# Battery.net
KiCad netlist of a schematic drawn in Altium Designer
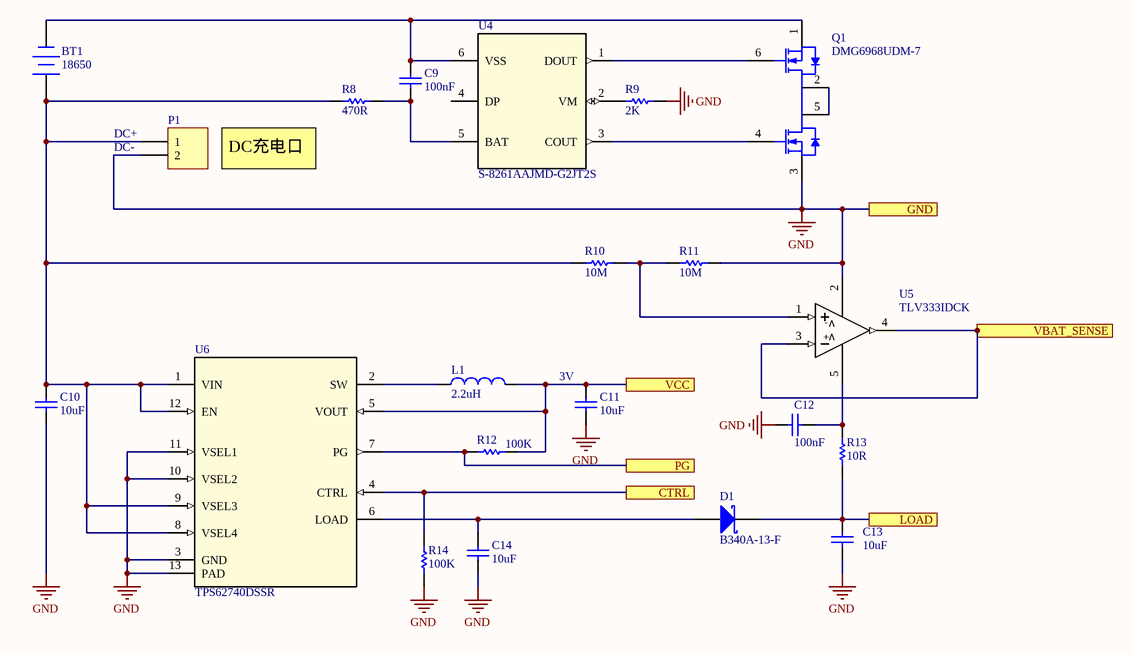
[diagram p0: Battery.SchDoc]

(export (version "E")
  (design (tool "Eeschema 10.0.6"))
  (components
    (comp (ref "BT1")
      (value "18650")
      (footprint "CP1X2")
      (description "18650单节直插电池仓")
      (libsource (lib "00Lib") (part "Battery_18650_DIP"))
    )
    (comp (ref "C9")
      (value "100nF")
      (footprint "R0603_C")
      (description "精度 ±10% \r\n容值 100nF \r\n额定电压 50V \r\n温漂系数（介质材料) X7R")
      (libsource (lib "00Lib") (part "100nF/0603/50V"))
    )
    (comp (ref "C10")
      (value "10uF")
      (footprint "R0805_C")
      (description "精度 ±10% \r\n容值 10uF \r\n额定电压 16V \r\n温漂系数（介质材料) X7R")
      (libsource (lib "00Lib") (part "10uF/0805/16V"))
    )
    (comp (ref "C11")
      (value "10uF")
      (footprint "R0805_C")
      (description "精度 ±10% \r\n容值 10uF \r\n额定电压 16V \r\n温漂系数（介质材料) X7R")
      (libsource (lib "00Lib") (part "10uF/0805/16V"))
    )
    (comp (ref "C12")
      (value "100nF")
      (footprint "R0603_C")
      (description "精度 ±10% \r\n容值 100nF \r\n额定电压 50V \r\n温漂系数（介质材料) X7R")
      (libsource (lib "00Lib") (part "100nF/0603/50V"))
    )
    (comp (ref "C13")
      (value "10uF")
      (footprint "R0805_C")
      (description "精度 ±10% \r\n容值 10uF \r\n额定电压 16V \r\n温漂系数（介质材料) X7R")
      (libsource (lib "00Lib") (part "10uF/0805/16V"))
    )
    (comp (ref "C14")
      (value "10uF")
      (footprint "R0805_C")
      (description "精度 ±10% \r\n容值 10uF \r\n额定电压 16V \r\n温漂系数（介质材料) X7R")
      (libsource (lib "00Lib") (part "10uF/0805/16V"))
    )
    (comp (ref "D1")
      (value "B340A-13-F")
      (footprint "SMA(DO-214AC)_S2")
      (description "直流反向耐压（Vr） 40V \r\n平均整流电流（Io） 3A \r\n正向压降（Vf） 550mV @ 3A")
      (libsource (lib "00Lib") (part "B340A-13-F"))
    )
    (comp (ref "L1")
      (value "2.2uH")
      (footprint "NR2016")
      (description "精度 ±20% \r\n饱和电流 1.3A \r\n温升电流1.15A\r\n直流电阻（内阻） 175mΩ \r\n电感值 2.2uH")
      (libsource (lib "00Lib") (part "2.2uH/NR2016"))
    )
    (comp (ref "P1")
      (value "Header 2")
      (footprint "CP1X2")
      (description "Header, 2-Pin")
      (libsource (lib "00Lib") (part "Header 2"))
    )
    (comp (ref "Q1")
      (value "DMG6968UDM-7")
      (footprint "DBV0006A_N")
      (libsource (lib "00Lib") (part "DMG6968UDM-7"))
    )
    (comp (ref "R8")
      (value "470R")
      (footprint "R0603_R")
      (description "精度 ±1% \r\n温度系数 ±100ppm/℃ \r\n功率 0.1W")
      (libsource (lib "00Lib") (part "470R/0603"))
    )
    (comp (ref "R9")
      (value "2K")
      (footprint "R0603_R")
      (description "精度 ±1% \r\n阻值 2kΩ \r\n温度系数 ±100ppm/℃ \r\n功率 0.1W")
      (libsource (lib "00Lib") (part "2K/0603"))
    )
    (comp (ref "R10")
      (value "10M")
      (footprint "R0603_R")
      (description "温度系数 ±250ppm/℃ \r\n精度 ±1% \r\n阻值 10MΩ \r\n功率 0.1W")
      (libsource (lib "00Lib") (part "10M/0603"))
    )
    (comp (ref "R11")
      (value "10M")
      (footprint "R0603_R")
      (description "温度系数 ±250ppm/℃ \r\n精度 ±1% \r\n阻值 10MΩ \r\n功率 0.1W")
      (libsource (lib "00Lib") (part "10M/0603"))
    )
    (comp (ref "R12")
      (value "100K")
      (footprint "R0603_R")
      (description "精度 ±1% \r\n阻值 100kΩ \r\n温度系数 ±100ppm/℃ \r\n功率 0.1W")
      (libsource (lib "00Lib") (part "100K/0603"))
    )
    (comp (ref "R13")
      (value "10R")
      (footprint "R0603_R")
      (description "精度 ±1% \r\n阻值 10Ω \r\n温度系数 ±100ppm/℃ \r\n功率 0.1W")
      (libsource (lib "00Lib") (part "10R/0603"))
    )
    (comp (ref "R14")
      (value "100K")
      (footprint "R0603_R")
      (description "精度 ±1% \r\n阻值 100kΩ \r\n温度系数 ±100ppm/℃ \r\n功率 0.1W")
      (libsource (lib "00Lib") (part "100K/0603"))
    )
    (comp (ref "U4")
      (value "S-8261AAJMD-G2JT2S")
      (footprint "DBV0006A_N")
      (description "单节电池保护芯片\r\n过充4.325V\r\n过放2.5V\r\n过流150mV")
      (libsource (lib "00Lib") (part "S-8261AAJMD-G2JT2S"))
    )
    (comp (ref "U5")
      (value "TLV333IDCK")
      (footprint "DCK0005A_N")
      (description "电源电压 1.8V ~ 5.5V, ±0.9V ~ 2.75V\r\n增益带宽积（GBP） 350kHz \r\n压摆率（SR） 0.16 V/us \r\n工作温度 -40°C ~ 125°C")
      (libsource (lib "00Lib") (part "TLV333IDCK"))
    )
    (comp (ref "U6")
      (value "TPS62740DSSR")
      (footprint "DSS0012A")
      (description "DCDC")
      (libsource (lib "00Lib") (part "TPS62740DSSR"))
    )
  )
  (nets
    (net (code "1") (name "/CTRL") (class "Default")
      (node (ref "R14") (pin "2") (pinfunction "2_2") (pintype "passive"))
      (node (ref "U6") (pin "4") (pinfunction "CTRL_4") (pintype "input"))
    )
    (net (code "2") (name "/LOAD") (class "Default")
      (node (ref "C13") (pin "2") (pinfunction "2_2") (pintype "passive"))
      (node (ref "D1") (pin "2") (pinfunction "K_2") (pintype "passive"))
      (node (ref "R13") (pin "2") (pinfunction "2_2") (pintype "passive"))
    )
    (net (code "3") (name "/PG") (class "Default")
      (node (ref "R12") (pin "1") (pinfunction "1_1") (pintype "passive"))
      (node (ref "U6") (pin "7") (pinfunction "PG_7") (pintype "output"))
    )
    (net (code "4") (name "/VBAT_SENSE") (class "Default")
      (node (ref "U5") (pin "3") (pinfunction "IN-_3") (pintype "input"))
      (node (ref "U5") (pin "4") (pinfunction "OUT_4") (pintype "output"))
    )
    (net (code "5") (name "/VCC") (class "Default")
      (node (ref "C11") (pin "2") (pinfunction "2_2") (pintype "passive"))
      (node (ref "L1") (pin "2") (pinfunction "2_2") (pintype "passive"))
      (node (ref "R12") (pin "2") (pinfunction "2_2") (pintype "passive"))
      (node (ref "U6") (pin "5") (pinfunction "VOUT_5") (pintype "input"))
    )
    (net (code "6") (name "GND") (class "Default")
      (node (ref "C10") (pin "1") (pinfunction "1_1") (pintype "passive"))
      (node (ref "C11") (pin "1") (pinfunction "1_1") (pintype "passive"))
      (node (ref "C12") (pin "1") (pinfunction "1_1") (pintype "passive"))
      (node (ref "C13") (pin "1") (pinfunction "1_1") (pintype "passive"))
      (node (ref "C14") (pin "1") (pinfunction "1_1") (pintype "passive"))
      (node (ref "P1") (pin "2") (pinfunction "2_2") (pintype "passive"))
      (node (ref "Q1") (pin "3") (pinfunction "S2_3") (pintype "passive"))
      (node (ref "R11") (pin "1") (pinfunction "1_1") (pintype "passive"))
      (node (ref "R14") (pin "1") (pinfunction "1_1") (pintype "passive"))
      (node (ref "R9") (pin "2") (pinfunction "2_2") (pintype "passive"))
      (node (ref "U5") (pin "2") (pinfunction "V-_2") (pintype "power_in"))
      (node (ref "U6") (pin "10") (pinfunction "VSEL2_10") (pintype "input"))
      (node (ref "U6") (pin "11") (pinfunction "VSEL1_11") (pintype "input"))
      (node (ref "U6") (pin "13") (pinfunction "PAD_13") (pintype "power_in"))
      (node (ref "U6") (pin "3") (pinfunction "GND_3") (pintype "power_in"))
    )
    (net (code "7") (name "Net-(BT1-+)") (class "Default")
      (node (ref "BT1") (pin "1") (pinfunction "+_1") (pintype "passive"))
      (node (ref "C10") (pin "2") (pinfunction "2_2") (pintype "passive"))
      (node (ref "P1") (pin "1") (pinfunction "1_1") (pintype "passive"))
      (node (ref "R10") (pin "2") (pinfunction "2_2") (pintype "passive"))
      (node (ref "R8") (pin "1") (pinfunction "1_1") (pintype "passive"))
      (node (ref "U6") (pin "1") (pinfunction "VIN_1") (pintype "power_in"))
      (node (ref "U6") (pin "12") (pinfunction "EN_12") (pintype "input"))
      (node (ref "U6") (pin "8") (pinfunction "VSEL4_8") (pintype "input"))
      (node (ref "U6") (pin "9") (pinfunction "VSEL3_9") (pintype "input"))
    )
    (net (code "8") (name "Net-(BT1--)") (class "Default")
      (node (ref "BT1") (pin "2") (pinfunction "-_2") (pintype "passive"))
      (node (ref "C9") (pin "1") (pinfunction "1_1") (pintype "passive"))
      (node (ref "Q1") (pin "1") (pinfunction "S1_1") (pintype "passive"))
      (node (ref "U4") (pin "6") (pinfunction "VSS_6") (pintype "passive"))
    )
    (net (code "9") (name "Net-(D1-A)") (class "Default")
      (node (ref "C14") (pin "2") (pinfunction "2_2") (pintype "passive"))
      (node (ref "D1") (pin "1") (pinfunction "A_1") (pintype "passive"))
      (node (ref "U6") (pin "6") (pinfunction "LOAD_6") (pintype "power_in"))
    )
    (net (code "10") (name "Net-(Q1-D1{slash}D2-Pad2)") (class "Default")
      (node (ref "Q1") (pin "2") (pinfunction "D1/D2_2") (pintype "passive"))
      (node (ref "Q1") (pin "5") (pinfunction "D1/D2_5") (pintype "passive"))
    )
    (net (code "11") (name "Net-(Q1-G1)") (class "Default")
      (node (ref "Q1") (pin "6") (pinfunction "G1_6") (pintype "passive"))
      (node (ref "U4") (pin "1") (pinfunction "DOUT_1") (pintype "output"))
    )
    (net (code "12") (name "Net-(Q1-G2)") (class "Default")
      (node (ref "Q1") (pin "4") (pinfunction "G2_4") (pintype "passive"))
      (node (ref "U4") (pin "3") (pinfunction "COUT_3") (pintype "output"))
    )
    (net (code "13") (name "Net-(U4-BAT)") (class "Default")
      (node (ref "C9") (pin "2") (pinfunction "2_2") (pintype "passive"))
      (node (ref "R8") (pin "2") (pinfunction "2_2") (pintype "passive"))
      (node (ref "U4") (pin "5") (pinfunction "BAT_5") (pintype "power_in"))
    )
    (net (code "14") (name "Net-(U4-VM)") (class "Default")
      (node (ref "R9") (pin "1") (pinfunction "1_1") (pintype "passive"))
      (node (ref "U4") (pin "2") (pinfunction "VM_2") (pintype "bidirectional"))
    )
    (net (code "15") (name "Net-(U5-IN+)") (class "Default")
      (node (ref "R10") (pin "1") (pinfunction "1_1") (pintype "passive"))
      (node (ref "R11") (pin "2") (pinfunction "2_2") (pintype "passive"))
      (node (ref "U5") (pin "1") (pinfunction "IN+_1") (pintype "input"))
    )
    (net (code "16") (name "Net-(U5-V+)") (class "Default")
      (node (ref "C12") (pin "2") (pinfunction "2_2") (pintype "passive"))
      (node (ref "R13") (pin "1") (pinfunction "1_1") (pintype "passive"))
      (node (ref "U5") (pin "5") (pinfunction "V+_5") (pintype "power_in"))
    )
    (net (code "17") (name "Net-(U6-SW)") (class "Default")
      (node (ref "L1") (pin "1") (pinfunction "1_1") (pintype "passive"))
      (node (ref "U6") (pin "2") (pinfunction "SW_2") (pintype "power_in"))
    )
    (net (code "18") (name "unconnected-(U4-DP-Pad4)") (class "Default")
      (node (ref "U4") (pin "4") (pinfunction "DP_4") (pintype "power_in"))
    )
  )
)
